# Connectors.net
KiCad netlist of a schematic drawn in Altium Designer
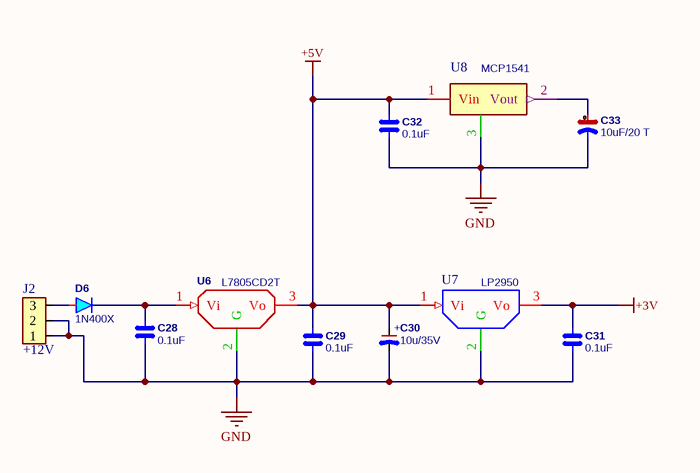
[diagram p0: Connectors.SchDoc]

(export (version "E")
  (design (tool "Eeschema 10.0.6"))
  (components
    (comp (ref "C28")
      (value "0.1uF")
      (footprint "CC2012-0805")
      (description "Capacitor SMD ceramic")
      (fields (field (name "PART#") "399-1170-1-ND"))
      (libsource (lib "VolcDB") (part "C-SMD CER"))
    )
    (comp (ref "C29")
      (value "0.1uF")
      (footprint "CC2012-0805")
      (description "Capacitor SMD ceramic")
      (fields (field (name "PART#") "399-1170-1-ND"))
      (libsource (lib "VolcDB") (part "C-SMD CER"))
    )
    (comp (ref "C30")
      (value "10u/35V")
      (footprint "CESMD-B")
      (description "Capacitor Electrolytic SMD")
      (fields (field (name "PART#") "PCE3413CT-ND"))
      (libsource (lib "VolcDB") (part "CESMD"))
    )
    (comp (ref "C31")
      (value "0.1uF")
      (footprint "CC2012-0805")
      (description "Capacitor SMD ceramic")
      (fields (field (name "PART#") "399-1170-1-ND"))
      (libsource (lib "VolcDB") (part "C-SMD CER"))
    )
    (comp (ref "C32")
      (value "0.1uF")
      (footprint "CC2012-0805")
      (description "Capacitor SMD ceramic")
      (fields (field (name "PART#") "399-1170-1-ND"))
      (libsource (lib "VolcDB") (part "C-SMD CER"))
    )
    (comp (ref "C33")
      (value "10uF/20 T")
      (footprint "CC3216-1206")
      (description "Capacitor Tantal")
      (fields (field (name "PART#") "399-5152-1-ND"))
      (libsource (lib "VolcDB") (part "C-SMD TAN"))
    )
    (comp (ref "D6")
      (value "1N400X")
      (footprint "DO-41")
      (description "Rectifier diode")
      (libsource (lib "VolcDB") (part "1N400X"))
    )
    (comp (ref "J2")
      (value "+12V")
      (footprint "6410/3pin")
      (description "Connector 3 pin")
      (libsource (lib "VolcDB") (part "CON3"))
    )
    (comp (ref "U6")
      (value "L7805CD2T")
      (footprint "D2PAK")
      (description "Positive  voltage regulator 5V/1.5A")
      (fields (field (name "PART#") "497-1171-1-ND"))
      (libsource (lib "VolcDB") (part "L7805CD2T"))
    )
    (comp (ref "U7")
      (value "LP2950")
      (footprint "DPak-369C-01")
      (description "Positive  voltage regulator 3V/100mA")
      (fields (field (name "PART#") "LP2950CDT-3.0RKGOSCT-ND"))
      (libsource (lib "VolcDB") (part "LP2950-DPak"))
    )
    (comp (ref "U8")
      (value "MCP1541")
      (footprint "SOT-23")
      (description "Voltage reference")
      (fields (field (name "PART#") "MCP1541T-I/TTCT-ND"))
      (libsource (lib "VolcDB") (part "MCP15xx"))
    )
  )
  (nets
    (net (code "1") (name "+3V") (class "Default")
      (node (ref "C31") (pin "2") (pinfunction "C2_2") (pintype "passive"))
      (node (ref "U7") (pin "3") (pinfunction "Vo_3") (pintype "power_in"))
    )
    (net (code "2") (name "+5V") (class "Default")
      (node (ref "C29") (pin "2") (pinfunction "C2_2") (pintype "passive"))
      (node (ref "C30") (pin "1") (pinfunction "+_1") (pintype "passive"))
      (node (ref "C32") (pin "2") (pinfunction "C2_2") (pintype "passive"))
      (node (ref "U6") (pin "3") (pinfunction "Vo_3") (pintype "power_in"))
      (node (ref "U7") (pin "1") (pinfunction "Vi_1") (pintype "input"))
      (node (ref "U8") (pin "1") (pinfunction "Vin_1") (pintype "power_in"))
    )
    (net (code "3") (name "GND") (class "Default")
      (node (ref "C28") (pin "1") (pinfunction "C1_1") (pintype "passive"))
      (node (ref "C29") (pin "1") (pinfunction "C1_1") (pintype "passive"))
      (node (ref "C30") (pin "2") (pinfunction "-_2") (pintype "passive"))
      (node (ref "C31") (pin "1") (pinfunction "C1_1") (pintype "passive"))
      (node (ref "C32") (pin "1") (pinfunction "C1_1") (pintype "passive"))
      (node (ref "C33") (pin "2") (pinfunction "C2_2") (pintype "passive"))
      (node (ref "J2") (pin "1") (pinfunction "1_1") (pintype "passive"))
      (node (ref "J2") (pin "2") (pinfunction "2_2") (pintype "passive"))
      (node (ref "U6") (pin "2") (pinfunction "G_2") (pintype "passive"))
      (node (ref "U7") (pin "2") (pinfunction "G_2") (pintype "passive"))
      (node (ref "U8") (pin "3") (pinfunction "Vss_3") (pintype "passive"))
    )
    (net (code "4") (name "Net-(C28-C2)") (class "Default")
      (node (ref "C28") (pin "2") (pinfunction "C2_2") (pintype "passive"))
      (node (ref "D6") (pin "2") (pinfunction "K_2") (pintype "passive"))
      (node (ref "U6") (pin "1") (pinfunction "Vi_1") (pintype "input"))
    )
    (net (code "5") (name "Net-(C33-C1)") (class "Default")
      (node (ref "C33") (pin "1") (pinfunction "C1_1") (pintype "passive"))
      (node (ref "U8") (pin "2") (pinfunction "Vout_2") (pintype "output"))
    )
    (net (code "6") (name "Net-(D6-A)") (class "Default")
      (node (ref "D6") (pin "1") (pinfunction "A_1") (pintype "passive"))
      (node (ref "J2") (pin "3") (pinfunction "3_3") (pintype "passive"))
    )
  )
)
